# SH1-POWER.net
KiCad netlist of a schematic drawn in Altium Designer
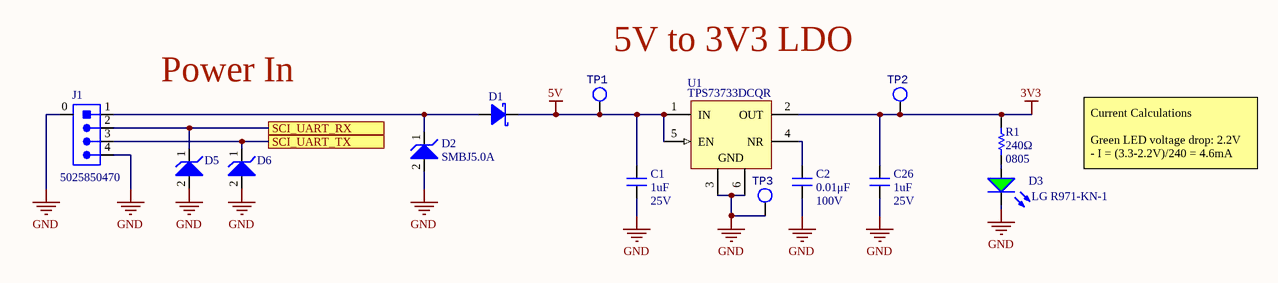
[diagram p0: SH1-POWER.SchDoc]

(export (version "E")
  (design (tool "Eeschema 10.0.6"))
  (components
    (comp (ref "C1")
      (value "~")
      (footprint "CAPC2012X140N")
      (description "CAP CER 1UF 25V X7R 0805")
      (fields
        (field (name "TOLERANCE") "10%")
        (field (name "CAPACITANCE") "1uF")
        (field (name "VOLTAGE RATING (DC)") "25V")
      )
      (libsource (lib "*") (part "CAP_1uF_25V_0805"))
    )
    (comp (ref "C2")
      (value "0.01μF")
      (footprint "CAP2012")
      (description "CAP CER 10000PF 100V X7R 0805")
      (fields
        (field (name "TOLERANCE") "10%")
        (field (name "VOLTAGE RATING") "100V")
        (field (name "Comment") "CAP_0.01uF_100V_0805")
      )
      (libsource (lib "UWRT_Schematic_Library_2020") (part "CAP_0.01uF_100V_0805"))
    )
    (comp (ref "C26")
      (value "~")
      (footprint "CAPC2012X140N")
      (description "CAP CER 1UF 25V X7R 0805")
      (fields
        (field (name "TOLERANCE") "10%")
        (field (name "CAPACITANCE") "1uF")
        (field (name "VOLTAGE RATING (DC)") "25V")
      )
      (libsource (lib "*") (part "CAP_1uF_25V_0805"))
    )
    (comp (ref "D1")
      (value "DIO_SCHOTTKY_30V_2A")
      (footprint "SOD-128")
      (description "DIODE SCHOTTKY 30V 2A PMDTM")
      (libsource (lib "UWRT_Schematic_Library_2020") (part "DIO_SCHOTTKY_30V_2A"))
    )
    (comp (ref "D2")
      (value "TVS_DIODE_UNIDIR_5V")
      (footprint "SMBJ5.0A")
      (description "TVS DIODE 5V 9.2V DO214AA")
      (fields (field (name "MANUFACTURER PART NUMBER 1") "SMBJ5.0A"))
      (libsource (lib "UWRT_Schematic_Library_2020") (part "TVS_DIODE_UNIDIR_5V"))
    )
    (comp (ref "D3")
      (value "LG R971-KN-1")
      (footprint "LED_0805_LINE")
      (description "LED GREEN DIFFUSED 0805 SMD")
      (libsource (lib "UWRT_Schematic_Library_2020") (part "DIO_LED_G"))
    )
    (comp (ref "D5")
      (value "TVS_DIODE_UNIDIR_3.3V")
      (footprint "SOD523")
      (description "TVS DIODE 3.3V 14.1V SOD523. Used to protect each connector input line going into the MCU.")
      (libsource (lib "UWRT_Schematic_Library_2020") (part "TVS_DIODE_UNIDIR_3.3V"))
    )
    (comp (ref "D6")
      (value "TVS_DIODE_UNIDIR_3.3V")
      (footprint "SOD523")
      (description "TVS DIODE 3.3V 14.1V SOD523. Used to protect each connector input line going into the MCU.")
      (libsource (lib "UWRT_Schematic_Library_2020") (part "TVS_DIODE_UNIDIR_3.3V"))
    )
    (comp (ref "J1")
      (value "CON_4M_SM_RA")
      (footprint "MOLEX-5025850470")
      (description "CONN HEADER SMD RIGHT ANGLE 1.5 MM PITCH")
      (fields (field (name "MANUFACTURER") "Molex") (field (name "MANUFACTOR NUMBER") "5025850470"))
      (libsource (lib "UWRT_Schematic_Library_2020") (part "CON_4M_SM_RA"))
    )
    (comp (ref "R1")
      (value "240")
      (footprint "RESC2012X60N")
      (description "RES 240 OHM 1% 1/8W 0805")
      (fields
        (field (name "TOLERANCE") "1%")
        (field (name "RESISTANCE") "240Ω")
        (field (name "CASE CODE (IMPERIAL)") "0805")
      )
      (libsource (lib "UWRT_Schematic_Library_2020") (part "RES_240Ω_0805_1%"))
    )
    (comp (ref "TP1")
      (value "TESTPOINT_LOOP")
      (footprint "TESTPOINT_LOOP")
      (description "Loop testpoint through-hole pad")
      (libsource (lib "UWRT_Schematic_Library_2020") (part "TESTPOINT_LOOP"))
    )
    (comp (ref "TP2")
      (value "TESTPOINT_LOOP")
      (footprint "TESTPOINT_LOOP")
      (description "Loop testpoint through-hole pad")
      (libsource (lib "UWRT_Schematic_Library_2020") (part "TESTPOINT_LOOP"))
    )
    (comp (ref "TP3")
      (value "TESTPOINT_LOOP")
      (footprint "TESTPOINT_LOOP")
      (description "Loop testpoint through-hole pad")
      (libsource (lib "UWRT_Schematic_Library_2020") (part "TESTPOINT_LOOP"))
    )
    (comp (ref "U1")
      (value "TPS73733DCQR")
      (footprint "UWRT_Footprint_Library_2020:SOT-223-6")
      (description "IC REG LINEAR 3.3V 1A SOT223-6")
      (fields (field (name "MANUFACTURER") "Texas Instruments"))
      (libsource (lib "Altium Content Vault") (part "LDO_3.3V_1A"))
    )
  )
  (nets
    (net (code "1") (name "/SCI_UART_RX") (class "Default")
      (node (ref "D5") (pin "1") (pinfunction "1_1") (pintype "passive"))
      (node (ref "J1") (pin "2") (pinfunction "2_2") (pintype "passive"))
    )
    (net (code "2") (name "/SCI_UART_TX") (class "Default")
      (node (ref "D6") (pin "1") (pinfunction "1_1") (pintype "passive"))
      (node (ref "J1") (pin "3") (pinfunction "3_3") (pintype "passive"))
    )
    (net (code "3") (name "3V3") (class "Default")
      (node (ref "C26") (pin "2") (pinfunction "2_2") (pintype "passive"))
      (node (ref "R1") (pin "2") (pinfunction "2_2") (pintype "passive"))
      (node (ref "TP2") (pin "1") (pintype "passive"))
      (node (ref "U1") (pin "2") (pinfunction "OUT_2") (pintype "power_in"))
    )
    (net (code "4") (name "5V") (class "Default")
      (node (ref "C1") (pin "1") (pinfunction "1_1") (pintype "passive"))
      (node (ref "D1") (pin "2") (pinfunction "Cathode_2") (pintype "passive"))
      (node (ref "TP1") (pin "1") (pintype "passive"))
      (node (ref "U1") (pin "1") (pinfunction "IN_1") (pintype "power_in"))
      (node (ref "U1") (pin "5") (pinfunction "EN_5") (pintype "input"))
    )
    (net (code "5") (name "GND") (class "Default")
      (node (ref "C1") (pin "2") (pinfunction "2_2") (pintype "passive"))
      (node (ref "C2") (pin "1") (pinfunction "1_1") (pintype "passive"))
      (node (ref "C26") (pin "1") (pinfunction "1_1") (pintype "passive"))
      (node (ref "D2") (pin "2") (pinfunction "2_2") (pintype "passive"))
      (node (ref "D3") (pin "2") (pinfunction "K_2") (pintype "passive"))
      (node (ref "D5") (pin "2") (pinfunction "2_2") (pintype "passive"))
      (node (ref "D6") (pin "2") (pinfunction "2_2") (pintype "passive"))
      (node (ref "J1") (pin "0") (pinfunction "0_0") (pintype "passive"))
      (node (ref "J1") (pin "4") (pinfunction "4_4") (pintype "passive"))
      (node (ref "TP3") (pin "1") (pintype "passive"))
      (node (ref "U1") (pin "3") (pinfunction "GND_3") (pintype "power_in"))
      (node (ref "U1") (pin "6") (pinfunction "GND_6") (pintype "power_in"))
    )
    (net (code "6") (name "Net-(D1-Anode)") (class "Default")
      (node (ref "D1") (pin "1") (pinfunction "Anode_1") (pintype "passive"))
      (node (ref "D2") (pin "1") (pinfunction "1_1") (pintype "passive"))
      (node (ref "J1") (pin "1") (pinfunction "1_1") (pintype "passive"))
    )
    (net (code "7") (name "Net-(D3-A)") (class "Default")
      (node (ref "D3") (pin "1") (pinfunction "A_1") (pintype "passive"))
      (node (ref "R1") (pin "1") (pinfunction "1_1") (pintype "passive"))
    )
    (net (code "8") (name "Net-(U1-NR)") (class "Default")
      (node (ref "C2") (pin "2") (pinfunction "2_2") (pintype "passive"))
      (node (ref "U1") (pin "4") (pinfunction "NR_4") (pintype "passive"))
    )
  )
)
